# T13_bikeseatdriver.net
KiCad netlist of a schematic drawn in EAGLE
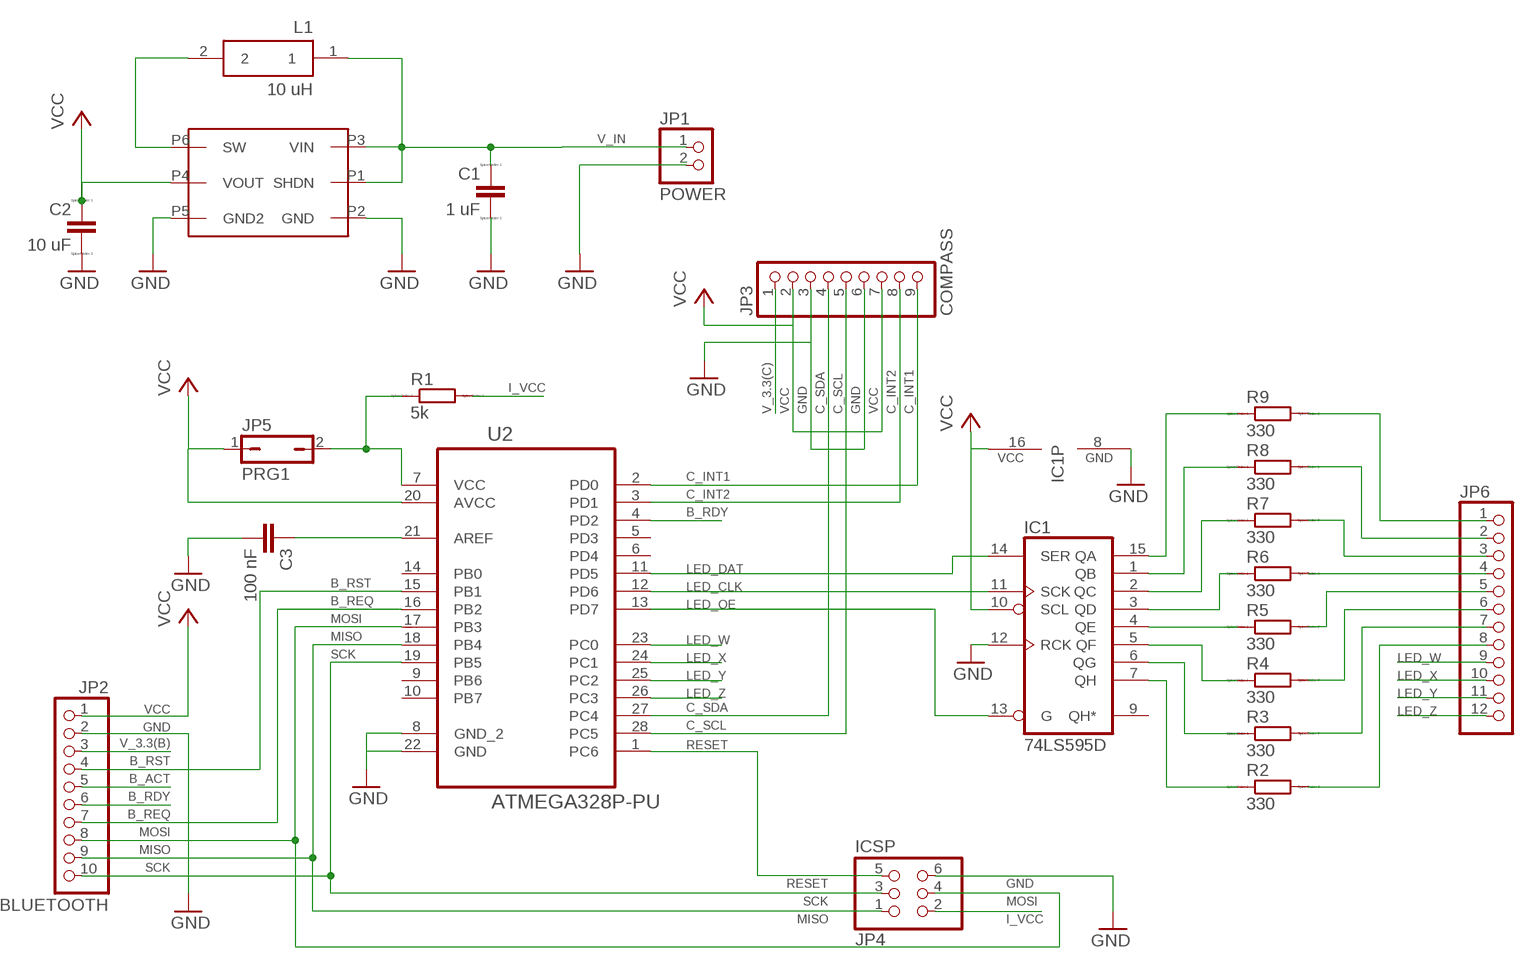
[diagram p0: schematic, sheet 1]

(export (version "E")
  (design (tool "Eeschema 10.0.6"))
  (components
    (comp (ref "C1")
      (value "1 uF")
      (footprint "eagle-import:C0603")
      (libsource (lib "eagle-import") (part "CC0603"))
    )
    (comp (ref "C2")
      (value "10 uF")
      (footprint "eagle-import:C0603")
      (libsource (lib "eagle-import") (part "CC0603"))
    )
    (comp (ref "C3")
      (value "100 nF")
      (footprint "eagle-import:C0603")
      (libsource (lib "eagle-import") (part "C-EUC0603"))
    )
    (comp (ref "IC1")
      (value "74LS595D")
      (footprint "eagle-import:SO16")
      (libsource (lib "eagle-import") (part "74595DLS"))
    )
    (comp (ref "JP1")
      (value "POWER")
      (footprint "eagle-import:1X02")
      (libsource (lib "eagle-import") (part "PINHD-1X2"))
    )
    (comp (ref "JP2")
      (value "BLUETOOTH")
      (footprint "eagle-import:1X10")
      (libsource (lib "eagle-import") (part "PINHD-1X10"))
    )
    (comp (ref "JP3")
      (value "COMPASS")
      (footprint "eagle-import:1X09")
      (libsource (lib "eagle-import") (part "PINHD-1X9"))
    )
    (comp (ref "JP4")
      (value "ICSP")
      (footprint "eagle-import:2X03")
      (libsource (lib "eagle-import") (part "PINHD-2X3"))
    )
    (comp (ref "JP5")
      (value "PRG1")
      (footprint "eagle-import:JP1")
      (libsource (lib "eagle-import") (part "JP1Q"))
    )
    (comp (ref "JP6")
      (value "PINHD-1X12")
      (footprint "eagle-import:1X12")
      (libsource (lib "eagle-import") (part "PINHD-1X12"))
    )
    (comp (ref "L1")
      (value "10 uH")
      (footprint "eagle-import:SRR0603")
      (libsource (lib "eagle-import") (part "SRR0603-100ML"))
    )
    (comp (ref "R1")
      (value "5k")
      (footprint "eagle-import:R0603")
      (libsource (lib "eagle-import") (part "RR0603"))
    )
    (comp (ref "R2")
      (value "330")
      (footprint "eagle-import:R0603")
      (libsource (lib "eagle-import") (part "RR0603"))
    )
    (comp (ref "R3")
      (value "330")
      (footprint "eagle-import:R0603")
      (libsource (lib "eagle-import") (part "RR0603"))
    )
    (comp (ref "R4")
      (value "330")
      (footprint "eagle-import:R0603")
      (libsource (lib "eagle-import") (part "RR0603"))
    )
    (comp (ref "R5")
      (value "330")
      (footprint "eagle-import:R0603")
      (libsource (lib "eagle-import") (part "RR0603"))
    )
    (comp (ref "R6")
      (value "330")
      (footprint "eagle-import:R0603")
      (libsource (lib "eagle-import") (part "RR0603"))
    )
    (comp (ref "R7")
      (value "330")
      (footprint "eagle-import:R0603")
      (libsource (lib "eagle-import") (part "RR0603"))
    )
    (comp (ref "R8")
      (value "330")
      (footprint "eagle-import:R0603")
      (libsource (lib "eagle-import") (part "RR0603"))
    )
    (comp (ref "R9")
      (value "330")
      (footprint "eagle-import:R0603")
      (libsource (lib "eagle-import") (part "RR0603"))
    )
    (comp (ref "U$2")
      (value "LTC3525")
      (footprint "eagle-import:6-LEAD-SC70")
      (libsource (lib "eagle-import") (part "LTC3525"))
    )
    (comp (ref "U2")
      (value "ATMEGA328P-PU")
      (footprint "eagle-import:DIP254P762X457-28")
      (libsource (lib "eagle-import") (part "ATMEGA328P-PU"))
    )
  )
  (nets
    (net (code "1") (name "/B_ACT") (class "Default")
      (node (ref "JP2") (pin "5") (pinfunction "5_5") (pintype "passive"))
    )
    (net (code "2") (name "/B_RDY") (class "Default")
      (node (ref "JP2") (pin "6") (pinfunction "6_6") (pintype "passive"))
      (node (ref "U2") (pin "4") (pinfunction "PD2_4") (pintype "bidirectional"))
    )
    (net (code "3") (name "/B_REQ") (class "Default")
      (node (ref "JP2") (pin "7") (pinfunction "7_7") (pintype "passive"))
      (node (ref "U2") (pin "16") (pinfunction "PB2_16") (pintype "bidirectional"))
    )
    (net (code "4") (name "/B_RST") (class "Default")
      (node (ref "JP2") (pin "4") (pinfunction "4_4") (pintype "passive"))
      (node (ref "U2") (pin "15") (pinfunction "PB1_15") (pintype "bidirectional"))
    )
    (net (code "5") (name "/C_INT1") (class "Default")
      (node (ref "JP3") (pin "9") (pinfunction "9_9") (pintype "passive"))
      (node (ref "U2") (pin "2") (pinfunction "PD0_2") (pintype "bidirectional"))
    )
    (net (code "6") (name "/C_INT2") (class "Default")
      (node (ref "JP3") (pin "8") (pinfunction "8_8") (pintype "passive"))
      (node (ref "U2") (pin "3") (pinfunction "PD1_3") (pintype "bidirectional"))
    )
    (net (code "7") (name "/C_SCL") (class "Default")
      (node (ref "JP3") (pin "5") (pinfunction "5_5") (pintype "passive"))
      (node (ref "U2") (pin "28") (pinfunction "PC5_28") (pintype "bidirectional"))
    )
    (net (code "8") (name "/C_SDA") (class "Default")
      (node (ref "JP3") (pin "4") (pinfunction "4_4") (pintype "passive"))
      (node (ref "U2") (pin "27") (pinfunction "PC4_27") (pintype "bidirectional"))
    )
    (net (code "9") (name "/I_VCC") (class "Default")
      (node (ref "JP4") (pin "2") (pinfunction "2_2") (pintype "passive"))
      (node (ref "R1") (pin "2") (pinfunction "2_2") (pintype "passive"))
    )
    (net (code "10") (name "/LED_CLK") (class "Default")
      (node (ref "IC1") (pin "11") (pinfunction "SCK_11") (pintype "input"))
      (node (ref "U2") (pin "12") (pinfunction "PD6_12") (pintype "bidirectional"))
    )
    (net (code "11") (name "/LED_DAT") (class "Default")
      (node (ref "IC1") (pin "14") (pinfunction "SER_14") (pintype "input"))
      (node (ref "U2") (pin "11") (pinfunction "PD5_11") (pintype "bidirectional"))
    )
    (net (code "12") (name "/LED_OE") (class "Default")
      (node (ref "IC1") (pin "13") (pinfunction "G_13") (pintype "input"))
      (node (ref "U2") (pin "13") (pinfunction "PD7_13") (pintype "bidirectional"))
    )
    (net (code "13") (name "/LED_W") (class "Default")
      (node (ref "JP6") (pin "9") (pinfunction "9_9") (pintype "passive"))
      (node (ref "U2") (pin "23") (pinfunction "PC0_23") (pintype "bidirectional"))
    )
    (net (code "14") (name "/LED_X") (class "Default")
      (node (ref "JP6") (pin "10") (pinfunction "10_10") (pintype "passive"))
      (node (ref "U2") (pin "24") (pinfunction "PC1_24") (pintype "bidirectional"))
    )
    (net (code "15") (name "/LED_Y") (class "Default")
      (node (ref "JP6") (pin "11") (pinfunction "11_11") (pintype "passive"))
      (node (ref "U2") (pin "25") (pinfunction "PC2_25") (pintype "bidirectional"))
    )
    (net (code "16") (name "/LED_Z") (class "Default")
      (node (ref "JP6") (pin "12") (pinfunction "12_12") (pintype "passive"))
      (node (ref "U2") (pin "26") (pinfunction "PC3_26") (pintype "bidirectional"))
    )
    (net (code "17") (name "/MISO") (class "Default")
      (node (ref "JP2") (pin "9") (pinfunction "9_9") (pintype "passive"))
      (node (ref "JP4") (pin "1") (pinfunction "1_1") (pintype "passive"))
      (node (ref "U2") (pin "18") (pinfunction "PB4_18") (pintype "bidirectional"))
    )
    (net (code "18") (name "/MOSI") (class "Default")
      (node (ref "JP2") (pin "8") (pinfunction "8_8") (pintype "passive"))
      (node (ref "JP4") (pin "4") (pinfunction "4_4") (pintype "passive"))
      (node (ref "U2") (pin "17") (pinfunction "PB3_17") (pintype "bidirectional"))
    )
    (net (code "19") (name "/RESET") (class "Default")
      (node (ref "JP4") (pin "5") (pinfunction "5_5") (pintype "passive"))
      (node (ref "U2") (pin "1") (pinfunction "PC6_1") (pintype "bidirectional"))
    )
    (net (code "20") (name "/SCK") (class "Default")
      (node (ref "JP2") (pin "10") (pinfunction "10_10") (pintype "passive"))
      (node (ref "JP4") (pin "3") (pinfunction "3_3") (pintype "passive"))
      (node (ref "U2") (pin "19") (pinfunction "PB5_19") (pintype "bidirectional"))
    )
    (net (code "21") (name "/V_3.3(B)") (class "Default")
      (node (ref "JP2") (pin "3") (pinfunction "3_3") (pintype "passive"))
    )
    (net (code "22") (name "/V_3.3(C)") (class "Default")
      (node (ref "JP3") (pin "1") (pinfunction "1_1") (pintype "passive"))
    )
    (net (code "23") (name "/V_IN") (class "Default")
      (node (ref "C1") (pin "1") (pinfunction "1_1") (pintype "passive"))
      (node (ref "JP1") (pin "1") (pinfunction "1_1") (pintype "passive"))
      (node (ref "L1") (pin "1") (pinfunction "1_1") (pintype "bidirectional"))
      (node (ref "U$2") (pin "P1") (pinfunction "SHDN_P1") (pintype "bidirectional"))
      (node (ref "U$2") (pin "P3") (pinfunction "VIN_P3") (pintype "bidirectional"))
    )
    (net (code "24") (name "GND") (class "Default")
      (node (ref "C1") (pin "2") (pinfunction "2_2") (pintype "passive"))
      (node (ref "C2") (pin "2") (pinfunction "2_2") (pintype "passive"))
      (node (ref "C3") (pin "2") (pinfunction "2_2") (pintype "passive"))
      (node (ref "IC1") (pin "12") (pinfunction "RCK_12") (pintype "input"))
      (node (ref "IC1") (pin "8") (pinfunction "GND_8") (pintype "power_in"))
      (node (ref "JP1") (pin "2") (pinfunction "2_2") (pintype "passive"))
      (node (ref "JP2") (pin "2") (pinfunction "2_2") (pintype "passive"))
      (node (ref "JP3") (pin "3") (pinfunction "3_3") (pintype "passive"))
      (node (ref "JP3") (pin "6") (pinfunction "6_6") (pintype "passive"))
      (node (ref "JP4") (pin "6") (pinfunction "6_6") (pintype "passive"))
      (node (ref "U$2") (pin "P2") (pinfunction "GND_P2") (pintype "bidirectional"))
      (node (ref "U$2") (pin "P5") (pinfunction "GND2_P5") (pintype "bidirectional"))
      (node (ref "U2") (pin "22") (pinfunction "GND_22") (pintype "passive"))
      (node (ref "U2") (pin "8") (pinfunction "GND_2_8") (pintype "passive"))
    )
    (net (code "25") (name "Net-(IC1A-QA)") (class "Default")
      (node (ref "IC1") (pin "15") (pinfunction "QA_15") (pintype "tri_state"))
      (node (ref "R9") (pin "1") (pinfunction "1_1") (pintype "passive"))
    )
    (net (code "26") (name "Net-(IC1A-QB)") (class "Default")
      (node (ref "IC1") (pin "1") (pinfunction "QB_1") (pintype "tri_state"))
      (node (ref "R8") (pin "1") (pinfunction "1_1") (pintype "passive"))
    )
    (net (code "27") (name "Net-(IC1A-QC)") (class "Default")
      (node (ref "IC1") (pin "2") (pinfunction "QC_2") (pintype "tri_state"))
      (node (ref "R7") (pin "1") (pinfunction "1_1") (pintype "passive"))
    )
    (net (code "28") (name "Net-(IC1A-QD)") (class "Default")
      (node (ref "IC1") (pin "3") (pinfunction "QD_3") (pintype "tri_state"))
      (node (ref "R6") (pin "1") (pinfunction "1_1") (pintype "passive"))
    )
    (net (code "29") (name "Net-(IC1A-QE)") (class "Default")
      (node (ref "IC1") (pin "4") (pinfunction "QE_4") (pintype "tri_state"))
      (node (ref "R5") (pin "1") (pinfunction "1_1") (pintype "passive"))
    )
    (net (code "30") (name "Net-(IC1A-QF)") (class "Default")
      (node (ref "IC1") (pin "5") (pinfunction "QF_5") (pintype "tri_state"))
      (node (ref "R4") (pin "1") (pinfunction "1_1") (pintype "passive"))
    )
    (net (code "31") (name "Net-(IC1A-QG)") (class "Default")
      (node (ref "IC1") (pin "6") (pinfunction "QG_6") (pintype "tri_state"))
      (node (ref "R3") (pin "1") (pinfunction "1_1") (pintype "passive"))
    )
    (net (code "32") (name "Net-(IC1A-QH)") (class "Default")
      (node (ref "IC1") (pin "7") (pinfunction "QH_7") (pintype "tri_state"))
      (node (ref "R2") (pin "1") (pinfunction "1_1") (pintype "passive"))
    )
    (net (code "33") (name "Net-(JP6-Pad1)") (class "Default")
      (node (ref "JP6") (pin "1") (pinfunction "1_1") (pintype "passive"))
      (node (ref "R9") (pin "2") (pinfunction "2_2") (pintype "passive"))
    )
    (net (code "34") (name "Net-(JP6-Pad2)") (class "Default")
      (node (ref "JP6") (pin "2") (pinfunction "2_2") (pintype "passive"))
      (node (ref "R8") (pin "2") (pinfunction "2_2") (pintype "passive"))
    )
    (net (code "35") (name "Net-(JP6-Pad3)") (class "Default")
      (node (ref "JP6") (pin "3") (pinfunction "3_3") (pintype "passive"))
      (node (ref "R7") (pin "2") (pinfunction "2_2") (pintype "passive"))
    )
    (net (code "36") (name "Net-(JP6-Pad4)") (class "Default")
      (node (ref "JP6") (pin "4") (pinfunction "4_4") (pintype "passive"))
      (node (ref "R6") (pin "2") (pinfunction "2_2") (pintype "passive"))
    )
    (net (code "37") (name "Net-(JP6-Pad5)") (class "Default")
      (node (ref "JP6") (pin "5") (pinfunction "5_5") (pintype "passive"))
      (node (ref "R5") (pin "2") (pinfunction "2_2") (pintype "passive"))
    )
    (net (code "38") (name "Net-(JP6-Pad6)") (class "Default")
      (node (ref "JP6") (pin "6") (pinfunction "6_6") (pintype "passive"))
      (node (ref "R4") (pin "2") (pinfunction "2_2") (pintype "passive"))
    )
    (net (code "39") (name "Net-(JP6-Pad7)") (class "Default")
      (node (ref "JP6") (pin "7") (pinfunction "7_7") (pintype "passive"))
      (node (ref "R3") (pin "2") (pinfunction "2_2") (pintype "passive"))
    )
    (net (code "40") (name "Net-(JP6-Pad8)") (class "Default")
      (node (ref "JP6") (pin "8") (pinfunction "8_8") (pintype "passive"))
      (node (ref "R2") (pin "2") (pinfunction "2_2") (pintype "passive"))
    )
    (net (code "41") (name "Net-(U$2-SW)") (class "Default")
      (node (ref "L1") (pin "2") (pinfunction "2_2") (pintype "bidirectional"))
      (node (ref "U$2") (pin "P6") (pinfunction "SW_P6") (pintype "bidirectional"))
    )
    (net (code "42") (name "Net-(U2-AREF)") (class "Default")
      (node (ref "C3") (pin "1") (pinfunction "1_1") (pintype "passive"))
      (node (ref "U2") (pin "21") (pinfunction "AREF_21") (pintype "input"))
    )
    (net (code "43") (name "Net-(U2-VCC)") (class "Default")
      (node (ref "JP5") (pin "2") (pinfunction "2_2") (pintype "passive"))
      (node (ref "R1") (pin "1") (pinfunction "1_1") (pintype "passive"))
      (node (ref "U2") (pin "7") (pinfunction "VCC_7") (pintype "power_in"))
    )
    (net (code "44") (name "VCC") (class "Default")
      (node (ref "C2") (pin "1") (pinfunction "1_1") (pintype "passive"))
      (node (ref "IC1") (pin "10") (pinfunction "SCL_10") (pintype "input"))
      (node (ref "IC1") (pin "16") (pinfunction "VCC_16") (pintype "power_in"))
      (node (ref "JP2") (pin "1") (pinfunction "1_1") (pintype "passive"))
      (node (ref "JP3") (pin "2") (pinfunction "2_2") (pintype "passive"))
      (node (ref "JP3") (pin "7") (pinfunction "7_7") (pintype "passive"))
      (node (ref "JP5") (pin "1") (pinfunction "1_1") (pintype "passive"))
      (node (ref "U$2") (pin "P4") (pinfunction "VOUT_P4") (pintype "bidirectional"))
      (node (ref "U2") (pin "20") (pinfunction "AVCC_20") (pintype "power_in"))
    )
    (net (code "45") (name "unconnected-(IC1A-QH*-Pad9)") (class "Default")
      (node (ref "IC1") (pin "9") (pinfunction "QH*_9") (pintype "tri_state"))
    )
    (net (code "46") (name "unconnected-(U2-PB0-Pad14)") (class "Default")
      (node (ref "U2") (pin "14") (pinfunction "PB0_14") (pintype "bidirectional"))
    )
    (net (code "47") (name "unconnected-(U2-PB6-Pad9)") (class "Default")
      (node (ref "U2") (pin "9") (pinfunction "PB6_9") (pintype "bidirectional"))
    )
    (net (code "48") (name "unconnected-(U2-PB7-Pad10)") (class "Default")
      (node (ref "U2") (pin "10") (pinfunction "PB7_10") (pintype "bidirectional"))
    )
    (net (code "49") (name "unconnected-(U2-PD3-Pad5)") (class "Default")
      (node (ref "U2") (pin "5") (pinfunction "PD3_5") (pintype "bidirectional"))
    )
    (net (code "50") (name "unconnected-(U2-PD4-Pad6)") (class "Default")
      (node (ref "U2") (pin "6") (pinfunction "PD4_6") (pintype "bidirectional"))
    )
  )
)
